# Schematic_6502.net
KiCad netlist of a schematic drawn in EasyEDA
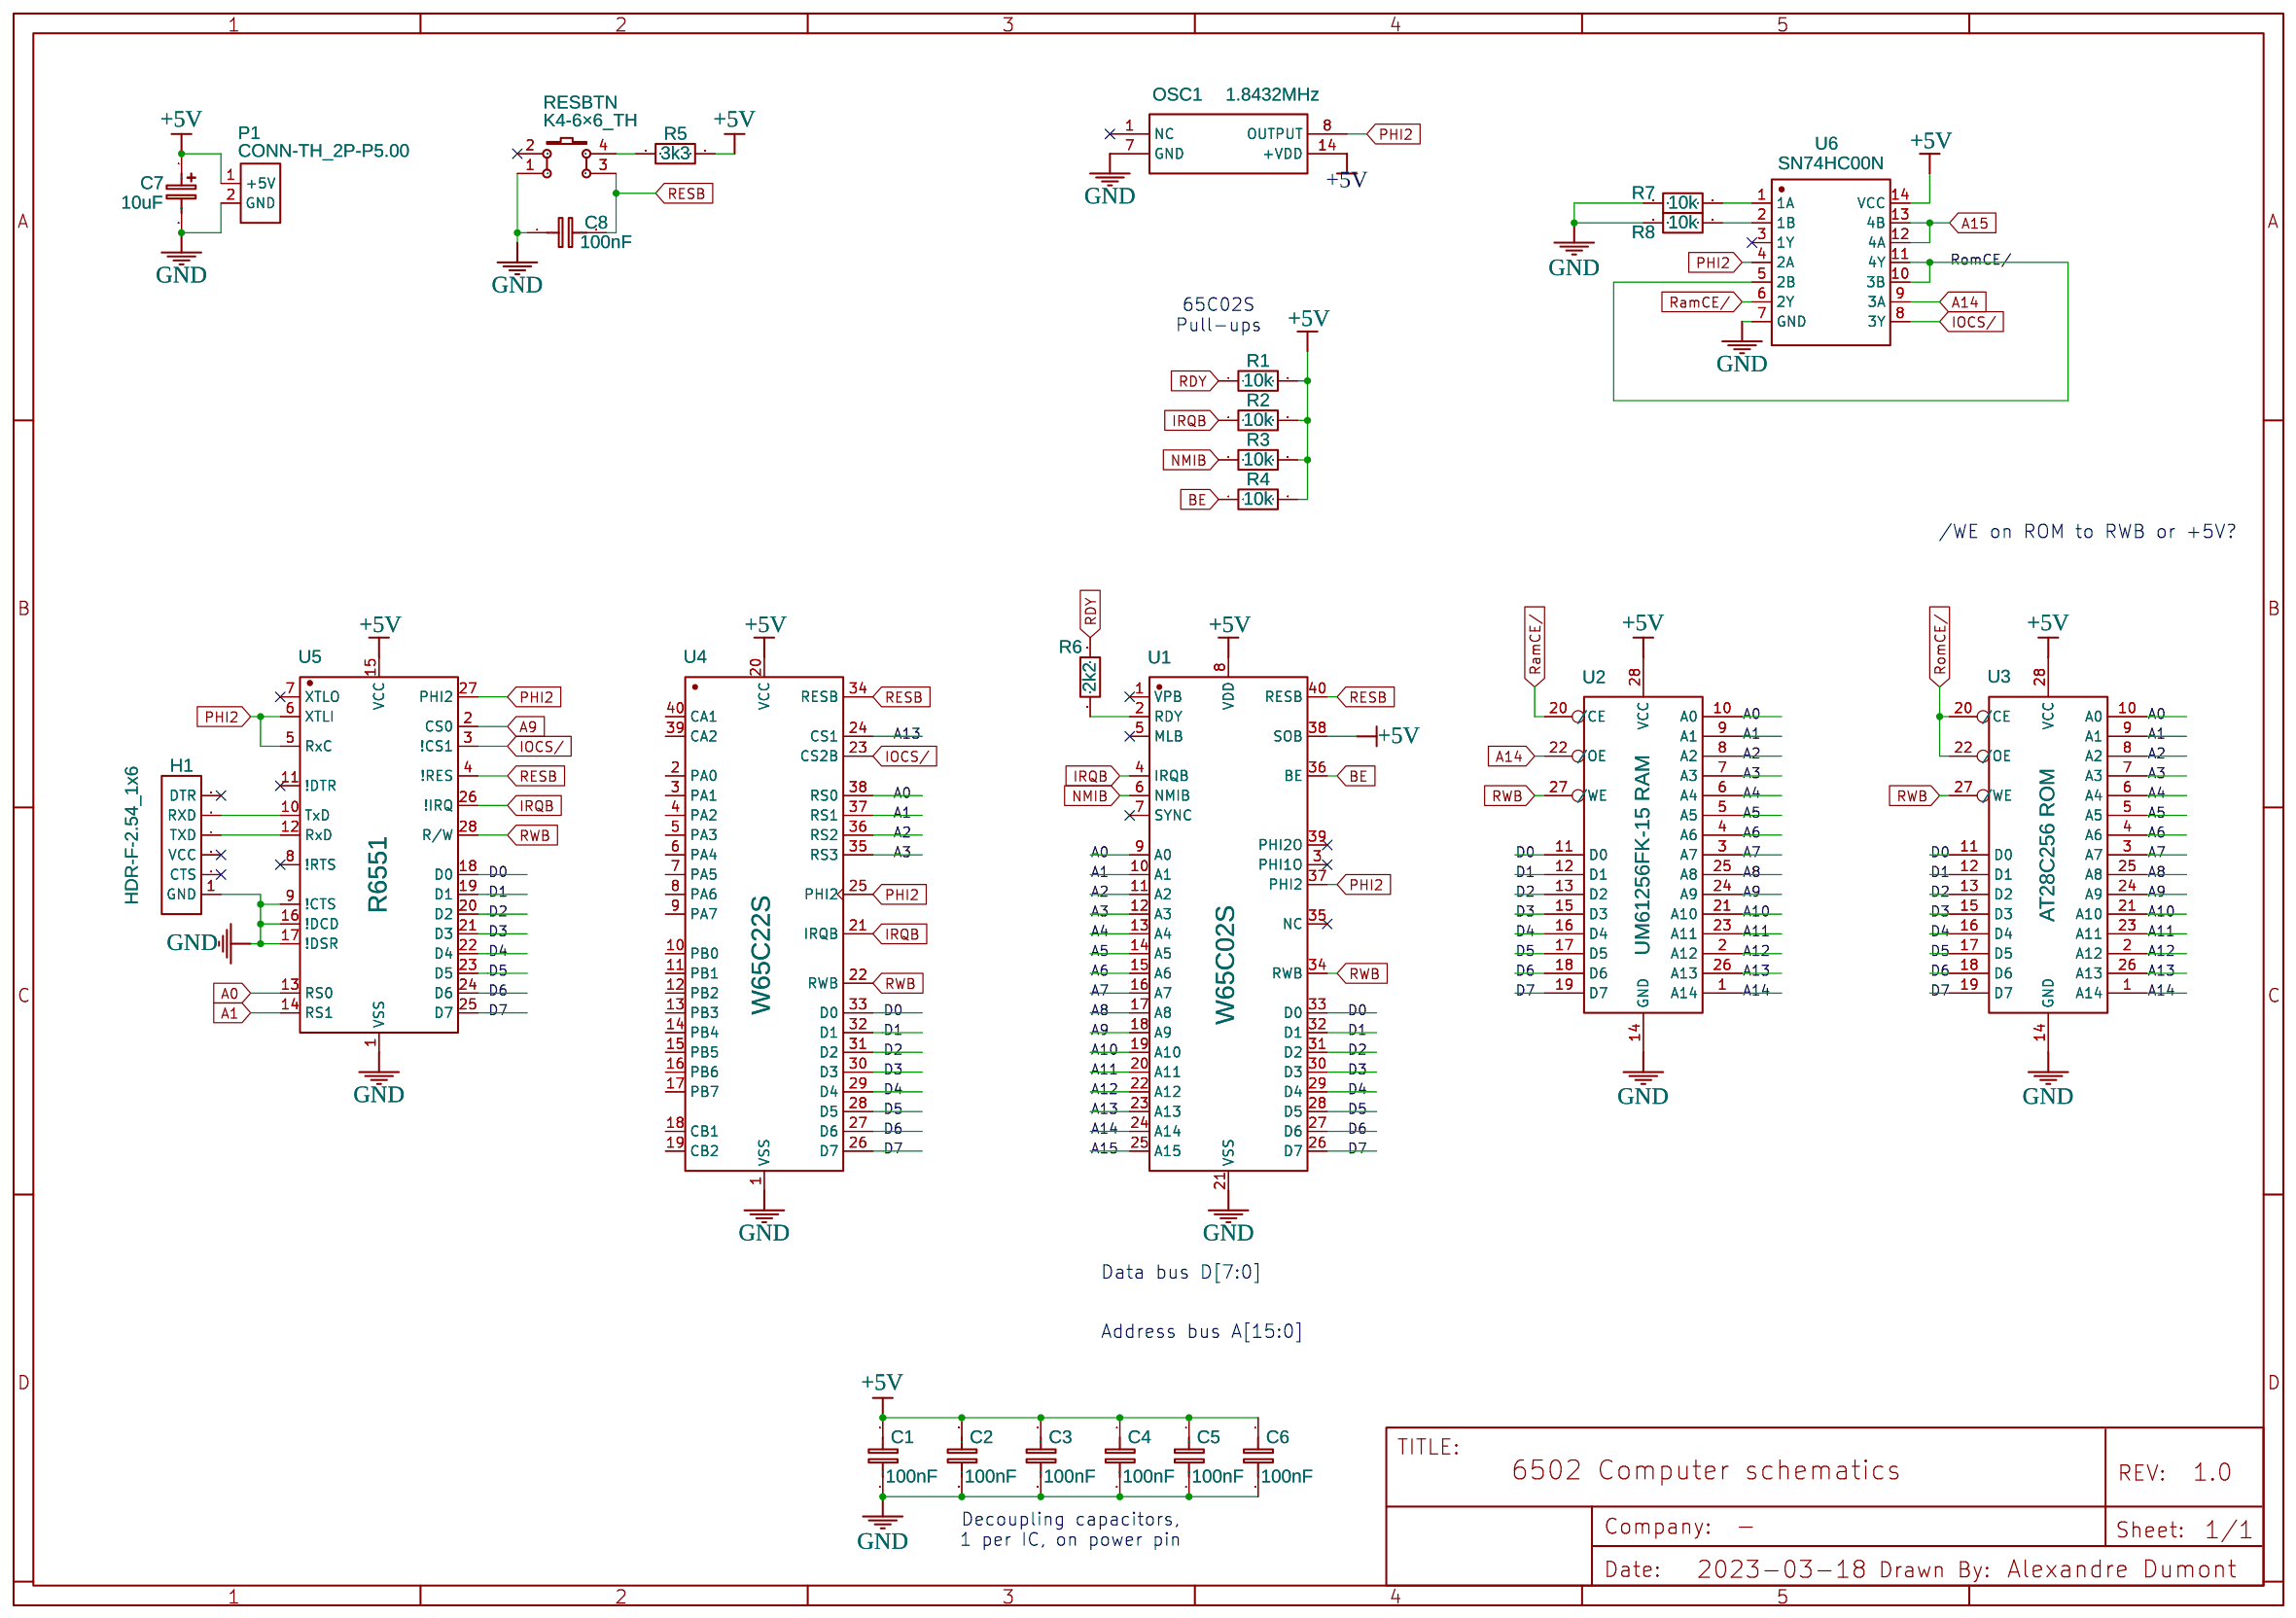
[diagram p0: schematic sheet]

(export (version "E")
  (design (tool "Eeschema 10.0.6"))
  (components
    (comp (ref "C1") (value "100nF") (libsource (lib "") (part "C_RAD-0.2_EU_1")))
    (comp (ref "C2") (value "100nF") (libsource (lib "") (part "C_RAD-0.2_EU_1")))
    (comp (ref "C3") (value "100nF") (libsource (lib "") (part "C_RAD-0.2_EU")))
    (comp (ref "C4") (value "100nF") (libsource (lib "") (part "C_RAD-0.2_EU")))
    (comp (ref "C5") (value "100nF") (libsource (lib "") (part "C_RAD-0.2_EU")))
    (comp (ref "C6") (value "100nF") (libsource (lib "") (part "C_RAD-0.2_EU")))
    (comp (ref "C7") (value "10uF") (libsource (lib "") (part "CE_TH_D5.0×F2.0_EU")))
    (comp (ref "C8") (value "100nF") (libsource (lib "") (part "C_RAD-0.2_EU_2")))
    (comp (ref "H1")
      (value "HDR-F-2.54_1x6")
      (fields (field (name "BOM_Supplier Part") "C40877"))
      (libsource (lib "") (part "HDR-F-2.54_1x6"))
    )
    (comp (ref "OSC1") (value "1.8432MHz") (libsource (lib "") (part "QX14T50B1.843200B50TT")))
    (comp (ref "P1") (value "CONN-TH_2P-P5.00") (libsource (lib "") (part "CONN-TH_2P-P5.00")))
    (comp (ref "R1") (value "10k") (libsource (lib "") (part "R_AXIAL-0.5_EU")))
    (comp (ref "R2") (value "10k") (libsource (lib "") (part "R_AXIAL-0.5_EU")))
    (comp (ref "R3") (value "10k") (libsource (lib "") (part "R_AXIAL-0.5_EU")))
    (comp (ref "R4") (value "10k") (libsource (lib "") (part "R_AXIAL-0.5_EU")))
    (comp (ref "R5") (value "3k3") (libsource (lib "") (part "R_AXIAL-0.5_EU")))
    (comp (ref "R6") (value "2k2") (libsource (lib "") (part "R_AXIAL-0.5_EU_1")))
    (comp (ref "R7") (value "10k") (libsource (lib "") (part "R_AXIAL-0.5_EU")))
    (comp (ref "R8") (value "10k") (libsource (lib "") (part "R_AXIAL-0.5_EU")))
    (comp (ref "RESBTN")
      (value "K4-6×6_TH")
      (fields
        (field (name "BOM_Manufacturer Part") "K2-1102DP-E4SW-04")
        (field (name "BOM_Supplier Part") "C136684")
      )
      (libsource (lib "") (part "K4-6×6_TH"))
    )
    (comp (ref "U1")
      (value "W65C02S")
      (fields
        (field (name "BOM_Manufacturer Part") "W65C02S6TPG-14")
        (field (name "BOM_Supplier Part") "955-W65C02S6TPG-14")
      )
      (libsource (lib "") (part "W65C02S6TPG-14 BUS GROUPED"))
    )
    (comp (ref "U2") (value "UM61256FK-15 RAM") (libsource (lib "") (part "AT28C256")))
    (comp (ref "U3") (value "AT28C256 ROM") (libsource (lib "") (part "AT28C256")))
    (comp (ref "U4")
      (value "W65C22S")
      (fields
        (field (name "BOM_Manufacturer Part") "W65C22S6TPG-14")
        (field (name "BOM_Supplier Part") "955-W65C22S6TPG-14")
      )
      (libsource (lib "") (part "W65C22S6TPG-14 BUS GROUPED"))
    )
    (comp (ref "U5") (value "R6551") (libsource (lib "") (part "R6551")))
    (comp (ref "U6")
      (value "SN74HC00N")
      (fields (field (name "BOM_Supplier Part") "C2902"))
      (libsource (lib "") (part "SN74HC00N"))
    )
  )
  (nets
    (net (code "1") (name "+5V") (class "Default")
      (node (ref "C1") (pin "1") (pinfunction "1_1") (pintype "unspecified"))
      (node (ref "C2") (pin "1") (pinfunction "1_1") (pintype "unspecified"))
      (node (ref "C3") (pin "1") (pinfunction "1_1") (pintype "unspecified"))
      (node (ref "C4") (pin "1") (pinfunction "1_1") (pintype "unspecified"))
      (node (ref "C5") (pin "1") (pinfunction "1_1") (pintype "unspecified"))
      (node (ref "C6") (pin "1") (pinfunction "1_1") (pintype "unspecified"))
      (node (ref "C7") (pin "1") (pinfunction "1_1") (pintype "unspecified"))
      (node (ref "OSC1") (pin "14") (pinfunction "+VDD_14") (pintype "bidirectional"))
      (node (ref "P1") (pin "1") (pinfunction "+5V_1") (pintype "unspecified"))
      (node (ref "R1") (pin "2") (pinfunction "2_2") (pintype "unspecified"))
      (node (ref "R2") (pin "2") (pinfunction "2_2") (pintype "unspecified"))
      (node (ref "R3") (pin "2") (pinfunction "2_2") (pintype "unspecified"))
      (node (ref "R4") (pin "2") (pinfunction "2_2") (pintype "unspecified"))
      (node (ref "R5") (pin "2") (pinfunction "2_2") (pintype "unspecified"))
      (node (ref "U1") (pin "38") (pinfunction "SOB_38") (pintype "unspecified"))
      (node (ref "U1") (pin "8") (pinfunction "VDD_8") (pintype "unspecified"))
      (node (ref "U2") (pin "28") (pinfunction "VCC_28") (pintype "unspecified"))
      (node (ref "U3") (pin "28") (pinfunction "VCC_28") (pintype "unspecified"))
      (node (ref "U4") (pin "20") (pinfunction "VCC_20") (pintype "passive"))
      (node (ref "U5") (pin "15") (pinfunction "VCC_15") (pintype "unspecified"))
      (node (ref "U6") (pin "14") (pinfunction "VCC_14") (pintype "unspecified"))
    )
    (net (code "2") (name "/A2") (class "Default")
      (node (ref "U1") (pin "11") (pinfunction "A2_11") (pintype "unspecified"))
      (node (ref "U2") (pin "8") (pinfunction "A2_8") (pintype "input"))
      (node (ref "U3") (pin "8") (pinfunction "A2_8") (pintype "input"))
      (node (ref "U4") (pin "36") (pinfunction "RS2_36") (pintype "input"))
    )
    (net (code "3") (name "/A3") (class "Default")
      (node (ref "U1") (pin "12") (pinfunction "A3_12") (pintype "unspecified"))
      (node (ref "U2") (pin "7") (pinfunction "A3_7") (pintype "input"))
      (node (ref "U3") (pin "7") (pinfunction "A3_7") (pintype "input"))
      (node (ref "U4") (pin "35") (pinfunction "RS3_35") (pintype "input"))
    )
    (net (code "4") (name "/A4") (class "Default")
      (node (ref "U1") (pin "13") (pinfunction "A4_13") (pintype "unspecified"))
      (node (ref "U2") (pin "6") (pinfunction "A4_6") (pintype "input"))
      (node (ref "U3") (pin "6") (pinfunction "A4_6") (pintype "input"))
    )
    (net (code "5") (name "/A5") (class "Default")
      (node (ref "U1") (pin "14") (pinfunction "A5_14") (pintype "unspecified"))
      (node (ref "U2") (pin "5") (pinfunction "A5_5") (pintype "input"))
      (node (ref "U3") (pin "5") (pinfunction "A5_5") (pintype "input"))
    )
    (net (code "6") (name "/A6") (class "Default")
      (node (ref "U1") (pin "15") (pinfunction "A6_15") (pintype "unspecified"))
      (node (ref "U2") (pin "4") (pinfunction "A6_4") (pintype "input"))
      (node (ref "U3") (pin "4") (pinfunction "A6_4") (pintype "input"))
    )
    (net (code "7") (name "/A7") (class "Default")
      (node (ref "U1") (pin "16") (pinfunction "A7_16") (pintype "unspecified"))
      (node (ref "U2") (pin "3") (pinfunction "A7_3") (pintype "input"))
      (node (ref "U3") (pin "3") (pinfunction "A7_3") (pintype "input"))
    )
    (net (code "8") (name "/A8") (class "Default")
      (node (ref "U1") (pin "17") (pinfunction "A8_17") (pintype "unspecified"))
      (node (ref "U2") (pin "25") (pinfunction "A8_25") (pintype "input"))
      (node (ref "U3") (pin "25") (pinfunction "A8_25") (pintype "input"))
    )
    (net (code "9") (name "/A10") (class "Default")
      (node (ref "U1") (pin "19") (pinfunction "A10_19") (pintype "unspecified"))
      (node (ref "U2") (pin "21") (pinfunction "A10_21") (pintype "input"))
      (node (ref "U3") (pin "21") (pinfunction "A10_21") (pintype "input"))
    )
    (net (code "10") (name "/A11") (class "Default")
      (node (ref "U1") (pin "20") (pinfunction "A11_20") (pintype "unspecified"))
      (node (ref "U2") (pin "23") (pinfunction "A11_23") (pintype "input"))
      (node (ref "U3") (pin "23") (pinfunction "A11_23") (pintype "input"))
    )
    (net (code "11") (name "/A12") (class "Default")
      (node (ref "U1") (pin "22") (pinfunction "A12_22") (pintype "unspecified"))
      (node (ref "U2") (pin "2") (pinfunction "A12_2") (pintype "input"))
      (node (ref "U3") (pin "2") (pinfunction "A12_2") (pintype "input"))
    )
    (net (code "12") (name "/A13") (class "Default")
      (node (ref "U1") (pin "23") (pinfunction "A13_23") (pintype "unspecified"))
      (node (ref "U2") (pin "26") (pinfunction "A13_26") (pintype "input"))
      (node (ref "U3") (pin "26") (pinfunction "A13_26") (pintype "input"))
      (node (ref "U4") (pin "24") (pinfunction "CS1_24") (pintype "unspecified"))
    )
    (net (code "13") (name "/D0") (class "Default")
      (node (ref "U1") (pin "33") (pinfunction "D0_33") (pintype "unspecified"))
      (node (ref "U2") (pin "11") (pinfunction "D0_11") (pintype "bidirectional"))
      (node (ref "U3") (pin "11") (pinfunction "D0_11") (pintype "bidirectional"))
      (node (ref "U4") (pin "33") (pinfunction "D0_33") (pintype "bidirectional"))
      (node (ref "U5") (pin "18") (pinfunction "D0_18") (pintype "unspecified"))
    )
    (net (code "14") (name "/D1") (class "Default")
      (node (ref "U1") (pin "32") (pinfunction "D1_32") (pintype "unspecified"))
      (node (ref "U2") (pin "12") (pinfunction "D1_12") (pintype "bidirectional"))
      (node (ref "U3") (pin "12") (pinfunction "D1_12") (pintype "bidirectional"))
      (node (ref "U4") (pin "32") (pinfunction "D1_32") (pintype "bidirectional"))
      (node (ref "U5") (pin "19") (pinfunction "D1_19") (pintype "unspecified"))
    )
    (net (code "15") (name "/D2") (class "Default")
      (node (ref "U1") (pin "31") (pinfunction "D2_31") (pintype "unspecified"))
      (node (ref "U2") (pin "13") (pinfunction "D2_13") (pintype "bidirectional"))
      (node (ref "U3") (pin "13") (pinfunction "D2_13") (pintype "bidirectional"))
      (node (ref "U4") (pin "31") (pinfunction "D2_31") (pintype "bidirectional"))
      (node (ref "U5") (pin "20") (pinfunction "D2_20") (pintype "unspecified"))
    )
    (net (code "16") (name "/D3") (class "Default")
      (node (ref "U1") (pin "30") (pinfunction "D3_30") (pintype "unspecified"))
      (node (ref "U2") (pin "15") (pinfunction "D3_15") (pintype "bidirectional"))
      (node (ref "U3") (pin "15") (pinfunction "D3_15") (pintype "bidirectional"))
      (node (ref "U4") (pin "30") (pinfunction "D3_30") (pintype "input"))
      (node (ref "U5") (pin "21") (pinfunction "D3_21") (pintype "unspecified"))
    )
    (net (code "17") (name "/D4") (class "Default")
      (node (ref "U1") (pin "29") (pinfunction "D4_29") (pintype "unspecified"))
      (node (ref "U2") (pin "16") (pinfunction "D4_16") (pintype "bidirectional"))
      (node (ref "U3") (pin "16") (pinfunction "D4_16") (pintype "bidirectional"))
      (node (ref "U4") (pin "29") (pinfunction "D4_29") (pintype "bidirectional"))
      (node (ref "U5") (pin "22") (pinfunction "D4_22") (pintype "unspecified"))
    )
    (net (code "18") (name "/D5") (class "Default")
      (node (ref "U1") (pin "28") (pinfunction "D5_28") (pintype "unspecified"))
      (node (ref "U2") (pin "17") (pinfunction "D5_17") (pintype "bidirectional"))
      (node (ref "U3") (pin "17") (pinfunction "D5_17") (pintype "bidirectional"))
      (node (ref "U4") (pin "28") (pinfunction "D5_28") (pintype "bidirectional"))
      (node (ref "U5") (pin "23") (pinfunction "D5_23") (pintype "unspecified"))
    )
    (net (code "19") (name "/D6") (class "Default")
      (node (ref "U1") (pin "27") (pinfunction "D6_27") (pintype "unspecified"))
      (node (ref "U2") (pin "18") (pinfunction "D6_18") (pintype "bidirectional"))
      (node (ref "U3") (pin "18") (pinfunction "D6_18") (pintype "bidirectional"))
      (node (ref "U4") (pin "27") (pinfunction "D6_27") (pintype "bidirectional"))
      (node (ref "U5") (pin "24") (pinfunction "D6_24") (pintype "unspecified"))
    )
    (net (code "20") (name "/D7") (class "Default")
      (node (ref "U1") (pin "26") (pinfunction "D7_26") (pintype "unspecified"))
      (node (ref "U2") (pin "19") (pinfunction "D7_19") (pintype "bidirectional"))
      (node (ref "U3") (pin "19") (pinfunction "D7_19") (pintype "bidirectional"))
      (node (ref "U4") (pin "26") (pinfunction "D7_26") (pintype "bidirectional"))
      (node (ref "U5") (pin "25") (pinfunction "D7_25") (pintype "unspecified"))
    )
    (net (code "21") (name "A0") (class "Default")
      (node (ref "U1") (pin "9") (pinfunction "A0_9") (pintype "unspecified"))
      (node (ref "U2") (pin "10") (pinfunction "A0_10") (pintype "input"))
      (node (ref "U3") (pin "10") (pinfunction "A0_10") (pintype "input"))
      (node (ref "U4") (pin "38") (pinfunction "RS0_38") (pintype "input"))
      (node (ref "U5") (pin "13") (pinfunction "RS0_13") (pintype "unspecified"))
    )
    (net (code "22") (name "A1") (class "Default")
      (node (ref "U1") (pin "10") (pinfunction "A1_10") (pintype "unspecified"))
      (node (ref "U2") (pin "9") (pinfunction "A1_9") (pintype "input"))
      (node (ref "U3") (pin "9") (pinfunction "A1_9") (pintype "input"))
      (node (ref "U4") (pin "37") (pinfunction "RS1_37") (pintype "input"))
      (node (ref "U5") (pin "14") (pinfunction "RS1_14") (pintype "unspecified"))
    )
    (net (code "23") (name "A9") (class "Default")
      (node (ref "U1") (pin "18") (pinfunction "A9_18") (pintype "unspecified"))
      (node (ref "U2") (pin "24") (pinfunction "A9_24") (pintype "input"))
      (node (ref "U3") (pin "24") (pinfunction "A9_24") (pintype "input"))
      (node (ref "U5") (pin "2") (pinfunction "CS0_2") (pintype "unspecified"))
    )
    (net (code "24") (name "A14") (class "Default")
      (node (ref "U1") (pin "24") (pinfunction "A14_24") (pintype "unspecified"))
      (node (ref "U2") (pin "1") (pinfunction "A14_1") (pintype "input"))
      (node (ref "U2") (pin "22") (pinfunction "/OE_22") (pintype "input"))
      (node (ref "U3") (pin "1") (pinfunction "A14_1") (pintype "input"))
      (node (ref "U6") (pin "9") (pinfunction "3A_9") (pintype "unspecified"))
    )
    (net (code "25") (name "A15") (class "Default")
      (node (ref "U1") (pin "25") (pinfunction "A15_25") (pintype "unspecified"))
      (node (ref "U6") (pin "12") (pinfunction "4A_12") (pintype "unspecified"))
      (node (ref "U6") (pin "13") (pinfunction "4B_13") (pintype "unspecified"))
    )
    (net (code "26") (name "BE") (class "Default")
      (node (ref "R4") (pin "1") (pinfunction "1_1") (pintype "unspecified"))
      (node (ref "U1") (pin "36") (pinfunction "BE_36") (pintype "unspecified"))
    )
    (net (code "27") (name "GND") (class "Default")
      (node (ref "C1") (pin "2") (pinfunction "2_2") (pintype "unspecified"))
      (node (ref "C2") (pin "2") (pinfunction "2_2") (pintype "unspecified"))
      (node (ref "C3") (pin "2") (pinfunction "2_2") (pintype "unspecified"))
      (node (ref "C4") (pin "2") (pinfunction "2_2") (pintype "unspecified"))
      (node (ref "C5") (pin "2") (pinfunction "2_2") (pintype "unspecified"))
      (node (ref "C6") (pin "2") (pinfunction "2_2") (pintype "unspecified"))
      (node (ref "C7") (pin "2") (pinfunction "2_2") (pintype "unspecified"))
      (node (ref "C8") (pin "1") (pinfunction "1_1") (pintype "unspecified"))
      (node (ref "H1") (pin "1") (pinfunction "GND_1") (pintype "input"))
      (node (ref "OSC1") (pin "7") (pinfunction "GND_7") (pintype "bidirectional"))
      (node (ref "P1") (pin "2") (pinfunction "GND_2") (pintype "unspecified"))
      (node (ref "R7") (pin "1") (pinfunction "1_1") (pintype "unspecified"))
      (node (ref "R8") (pin "1") (pinfunction "1_1") (pintype "unspecified"))
      (node (ref "RESBTN") (pin "1") (pinfunction "1_1") (pintype "unspecified"))
      (node (ref "U1") (pin "21") (pinfunction "VSS_21") (pintype "unspecified"))
      (node (ref "U2") (pin "14") (pinfunction "GND_14") (pintype "unspecified"))
      (node (ref "U3") (pin "14") (pinfunction "GND_14") (pintype "unspecified"))
      (node (ref "U4") (pin "1") (pinfunction "VSS_1") (pintype "passive"))
      (node (ref "U5") (pin "1") (pinfunction "VSS_1") (pintype "unspecified"))
      (node (ref "U5") (pin "16") (pinfunction "!DCD_16") (pintype "unspecified"))
      (node (ref "U5") (pin "17") (pinfunction "!DSR_17") (pintype "unspecified"))
      (node (ref "U5") (pin "9") (pinfunction "!CTS_9") (pintype "unspecified"))
      (node (ref "U6") (pin "7") (pinfunction "GND_7") (pintype "unspecified"))
    )
    (net (code "28") (name "IOCS{slash}") (class "Default")
      (node (ref "U4") (pin "23") (pinfunction "CS2B_23") (pintype "unspecified"))
      (node (ref "U5") (pin "3") (pinfunction "!CS1_3") (pintype "unspecified"))
      (node (ref "U6") (pin "8") (pinfunction "3Y_8") (pintype "unspecified"))
    )
    (net (code "29") (name "IRQB") (class "Default")
      (node (ref "R2") (pin "1") (pinfunction "1_1") (pintype "unspecified"))
      (node (ref "U1") (pin "4") (pinfunction "IRQB_4") (pintype "unspecified"))
      (node (ref "U4") (pin "21") (pinfunction "IRQB_21") (pintype "output"))
      (node (ref "U5") (pin "26") (pinfunction "!IRQ_26") (pintype "unspecified"))
    )
    (net (code "30") (name "NMIB") (class "Default")
      (node (ref "R3") (pin "1") (pinfunction "1_1") (pintype "unspecified"))
      (node (ref "U1") (pin "6") (pinfunction "NMIB_6") (pintype "unspecified"))
    )
    (net (code "31") (name "Net-(H1-RXD)") (class "Default")
      (node (ref "H1") (pin "5") (pinfunction "RXD_5") (pintype "input"))
      (node (ref "U5") (pin "10") (pinfunction "TxD_10") (pintype "unspecified"))
    )
    (net (code "32") (name "Net-(H1-TXD)") (class "Default")
      (node (ref "H1") (pin "4") (pinfunction "TXD_4") (pintype "input"))
      (node (ref "U5") (pin "12") (pinfunction "RxD_12") (pintype "unspecified"))
    )
    (net (code "33") (name "Net-(R5-Pad1)") (class "Default")
      (node (ref "R5") (pin "1") (pinfunction "1_1") (pintype "unspecified"))
      (node (ref "RESBTN") (pin "4") (pinfunction "4_4") (pintype "unspecified"))
    )
    (net (code "34") (name "Net-(U1-RDY)") (class "Default")
      (node (ref "R6") (pin "2") (pinfunction "2_2") (pintype "unspecified"))
      (node (ref "U1") (pin "2") (pinfunction "RDY_2") (pintype "unspecified"))
    )
    (net (code "35") (name "Net-(U6-1A)") (class "Default")
      (node (ref "R7") (pin "2") (pinfunction "2_2") (pintype "unspecified"))
      (node (ref "U6") (pin "1") (pinfunction "1A_1") (pintype "unspecified"))
    )
    (net (code "36") (name "Net-(U6-1B)") (class "Default")
      (node (ref "R8") (pin "2") (pinfunction "2_2") (pintype "unspecified"))
      (node (ref "U6") (pin "2") (pinfunction "1B_2") (pintype "unspecified"))
    )
    (net (code "37") (name "PHI2") (class "Default")
      (node (ref "OSC1") (pin "8") (pinfunction "OUTPUT_8") (pintype "bidirectional"))
      (node (ref "U1") (pin "37") (pinfunction "PHI2_37") (pintype "unspecified"))
      (node (ref "U4") (pin "25") (pinfunction "PHI2_25") (pintype "input"))
      (node (ref "U5") (pin "27") (pinfunction "PHI2_27") (pintype "unspecified"))
      (node (ref "U5") (pin "5") (pinfunction "RxC_5") (pintype "unspecified"))
      (node (ref "U5") (pin "6") (pinfunction "XTLI_6") (pintype "unspecified"))
      (node (ref "U6") (pin "4") (pinfunction "2A_4") (pintype "unspecified"))
    )
    (net (code "38") (name "RDY") (class "Default")
      (node (ref "R1") (pin "1") (pinfunction "1_1") (pintype "unspecified"))
      (node (ref "R6") (pin "1") (pinfunction "1_1") (pintype "unspecified"))
    )
    (net (code "39") (name "RESB") (class "Default")
      (node (ref "C8") (pin "2") (pinfunction "2_2") (pintype "unspecified"))
      (node (ref "RESBTN") (pin "3") (pinfunction "3_3") (pintype "unspecified"))
      (node (ref "U1") (pin "40") (pinfunction "RESB_40") (pintype "unspecified"))
      (node (ref "U4") (pin "34") (pinfunction "RESB_34") (pintype "input"))
      (node (ref "U5") (pin "4") (pinfunction "!RES_4") (pintype "unspecified"))
    )
    (net (code "40") (name "RWB") (class "Default")
      (node (ref "U1") (pin "34") (pinfunction "RWB_34") (pintype "unspecified"))
      (node (ref "U2") (pin "27") (pinfunction "/WE_27") (pintype "input"))
      (node (ref "U3") (pin "27") (pinfunction "/WE_27") (pintype "input"))
      (node (ref "U4") (pin "22") (pinfunction "RWB_22") (pintype "input"))
      (node (ref "U5") (pin "28") (pinfunction "R/W_28") (pintype "unspecified"))
    )
    (net (code "41") (name "RamCE{slash}") (class "Default")
      (node (ref "U2") (pin "20") (pinfunction "/CE_20") (pintype "input"))
      (node (ref "U6") (pin "6") (pinfunction "2Y_6") (pintype "unspecified"))
    )
    (net (code "42") (name "RomCE{slash}") (class "Default")
      (node (ref "U3") (pin "20") (pinfunction "/CE_20") (pintype "input"))
      (node (ref "U3") (pin "22") (pinfunction "/OE_22") (pintype "input"))
      (node (ref "U6") (pin "10") (pinfunction "3B_10") (pintype "unspecified"))
      (node (ref "U6") (pin "11") (pinfunction "4Y_11") (pintype "unspecified"))
      (node (ref "U6") (pin "5") (pinfunction "2B_5") (pintype "unspecified"))
    )
    (net (code "43") (name "unconnected-(H1-CTS-Pad2)") (class "Default")
      (node (ref "H1") (pin "2") (pinfunction "CTS_2") (pintype "input+no_connect"))
    )
    (net (code "44") (name "unconnected-(H1-DTR-Pad6)") (class "Default")
      (node (ref "H1") (pin "6") (pinfunction "DTR_6") (pintype "input+no_connect"))
    )
    (net (code "45") (name "unconnected-(H1-VCC-Pad3)") (class "Default")
      (node (ref "H1") (pin "3") (pinfunction "VCC_3") (pintype "input+no_connect"))
    )
    (net (code "46") (name "unconnected-(OSC1-NC-Pad1)") (class "Default")
      (node (ref "OSC1") (pin "1") (pinfunction "NC_1") (pintype "bidirectional+no_connect"))
    )
    (net (code "47") (name "unconnected-(RESBTN-Pad2)") (class "Default")
      (node (ref "RESBTN") (pin "2") (pinfunction "2_2") (pintype "unspecified+no_connect"))
    )
    (net (code "48") (name "unconnected-(U1-MLB-Pad5)") (class "Default")
      (node (ref "U1") (pin "5") (pinfunction "MLB_5") (pintype "unspecified+no_connect"))
    )
    (net (code "49") (name "unconnected-(U1-NC-Pad35)") (class "Default")
      (node (ref "U1") (pin "35") (pinfunction "NC_35") (pintype "unspecified+no_connect"))
    )
    (net (code "50") (name "unconnected-(U1-PHI1O-Pad3)") (class "Default")
      (node (ref "U1") (pin "3") (pinfunction "PHI1O_3") (pintype "unspecified+no_connect"))
    )
    (net (code "51") (name "unconnected-(U1-PHI2O-Pad39)") (class "Default")
      (node (ref "U1") (pin "39") (pinfunction "PHI2O_39") (pintype "unspecified+no_connect"))
    )
    (net (code "52") (name "unconnected-(U1-SYNC-Pad7)") (class "Default")
      (node (ref "U1") (pin "7") (pinfunction "SYNC_7") (pintype "unspecified+no_connect"))
    )
    (net (code "53") (name "unconnected-(U1-VPB-Pad1)") (class "Default")
      (node (ref "U1") (pin "1") (pinfunction "VPB_1") (pintype "unspecified+no_connect"))
    )
    (net (code "54") (name "unconnected-(U4-CA1-Pad40)") (class "Default")
      (node (ref "U4") (pin "40") (pinfunction "CA1_40") (pintype "unspecified"))
    )
    (net (code "55") (name "unconnected-(U4-CA2-Pad39)") (class "Default")
      (node (ref "U4") (pin "39") (pinfunction "CA2_39") (pintype "unspecified"))
    )
    (net (code "56") (name "unconnected-(U4-CB1-Pad18)") (class "Default")
      (node (ref "U4") (pin "18") (pinfunction "CB1_18") (pintype "unspecified"))
    )
    (net (code "57") (name "unconnected-(U4-CB2-Pad19)") (class "Default")
      (node (ref "U4") (pin "19") (pinfunction "CB2_19") (pintype "unspecified"))
    )
    (net (code "58") (name "unconnected-(U4-PA0-Pad2)") (class "Default")
      (node (ref "U4") (pin "2") (pinfunction "PA0_2") (pintype "bidirectional"))
    )
    (net (code "59") (name "unconnected-(U4-PA1-Pad3)") (class "Default")
      (node (ref "U4") (pin "3") (pinfunction "PA1_3") (pintype "bidirectional"))
    )
    (net (code "60") (name "unconnected-(U4-PA2-Pad4)") (class "Default")
      (node (ref "U4") (pin "4") (pinfunction "PA2_4") (pintype "bidirectional"))
    )
    (net (code "61") (name "unconnected-(U4-PA3-Pad5)") (class "Default")
      (node (ref "U4") (pin "5") (pinfunction "PA3_5") (pintype "bidirectional"))
    )
    (net (code "62") (name "unconnected-(U4-PA4-Pad6)") (class "Default")
      (node (ref "U4") (pin "6") (pinfunction "PA4_6") (pintype "bidirectional"))
    )
    (net (code "63") (name "unconnected-(U4-PA5-Pad7)") (class "Default")
      (node (ref "U4") (pin "7") (pinfunction "PA5_7") (pintype "bidirectional"))
    )
    (net (code "64") (name "unconnected-(U4-PA6-Pad8)") (class "Default")
      (node (ref "U4") (pin "8") (pinfunction "PA6_8") (pintype "bidirectional"))
    )
    (net (code "65") (name "unconnected-(U4-PA7-Pad9)") (class "Default")
      (node (ref "U4") (pin "9") (pinfunction "PA7_9") (pintype "bidirectional"))
    )
    (net (code "66") (name "unconnected-(U4-PB0-Pad10)") (class "Default")
      (node (ref "U4") (pin "10") (pinfunction "PB0_10") (pintype "bidirectional"))
    )
    (net (code "67") (name "unconnected-(U4-PB1-Pad11)") (class "Default")
      (node (ref "U4") (pin "11") (pinfunction "PB1_11") (pintype "bidirectional"))
    )
    (net (code "68") (name "unconnected-(U4-PB2-Pad12)") (class "Default")
      (node (ref "U4") (pin "12") (pinfunction "PB2_12") (pintype "bidirectional"))
    )
    (net (code "69") (name "unconnected-(U4-PB3-Pad13)") (class "Default")
      (node (ref "U4") (pin "13") (pinfunction "PB3_13") (pintype "bidirectional"))
    )
    (net (code "70") (name "unconnected-(U4-PB4-Pad14)") (class "Default")
      (node (ref "U4") (pin "14") (pinfunction "PB4_14") (pintype "bidirectional"))
    )
    (net (code "71") (name "unconnected-(U4-PB5-Pad15)") (class "Default")
      (node (ref "U4") (pin "15") (pinfunction "PB5_15") (pintype "bidirectional"))
    )
    (net (code "72") (name "unconnected-(U4-PB6-Pad16)") (class "Default")
      (node (ref "U4") (pin "16") (pinfunction "PB6_16") (pintype "bidirectional"))
    )
    (net (code "73") (name "unconnected-(U4-PB7-Pad17)") (class "Default")
      (node (ref "U4") (pin "17") (pinfunction "PB7_17") (pintype "bidirectional"))
    )
    (net (code "74") (name "unconnected-(U5-!DTR-Pad11)") (class "Default")
      (node (ref "U5") (pin "11") (pinfunction "!DTR_11") (pintype "unspecified+no_connect"))
    )
    (net (code "75") (name "unconnected-(U5-!RTS-Pad8)") (class "Default")
      (node (ref "U5") (pin "8") (pinfunction "!RTS_8") (pintype "unspecified+no_connect"))
    )
    (net (code "76") (name "unconnected-(U5-XTLO-Pad7)") (class "Default")
      (node (ref "U5") (pin "7") (pinfunction "XTLO_7") (pintype "unspecified+no_connect"))
    )
    (net (code "77") (name "unconnected-(U6-1Y-Pad3)") (class "Default")
      (node (ref "U6") (pin "3") (pinfunction "1Y_3") (pintype "unspecified+no_connect"))
    )
  )
)
